# C_Arduino_MEGA2560_ref.net
KiCad netlist of a schematic drawn in EAGLE
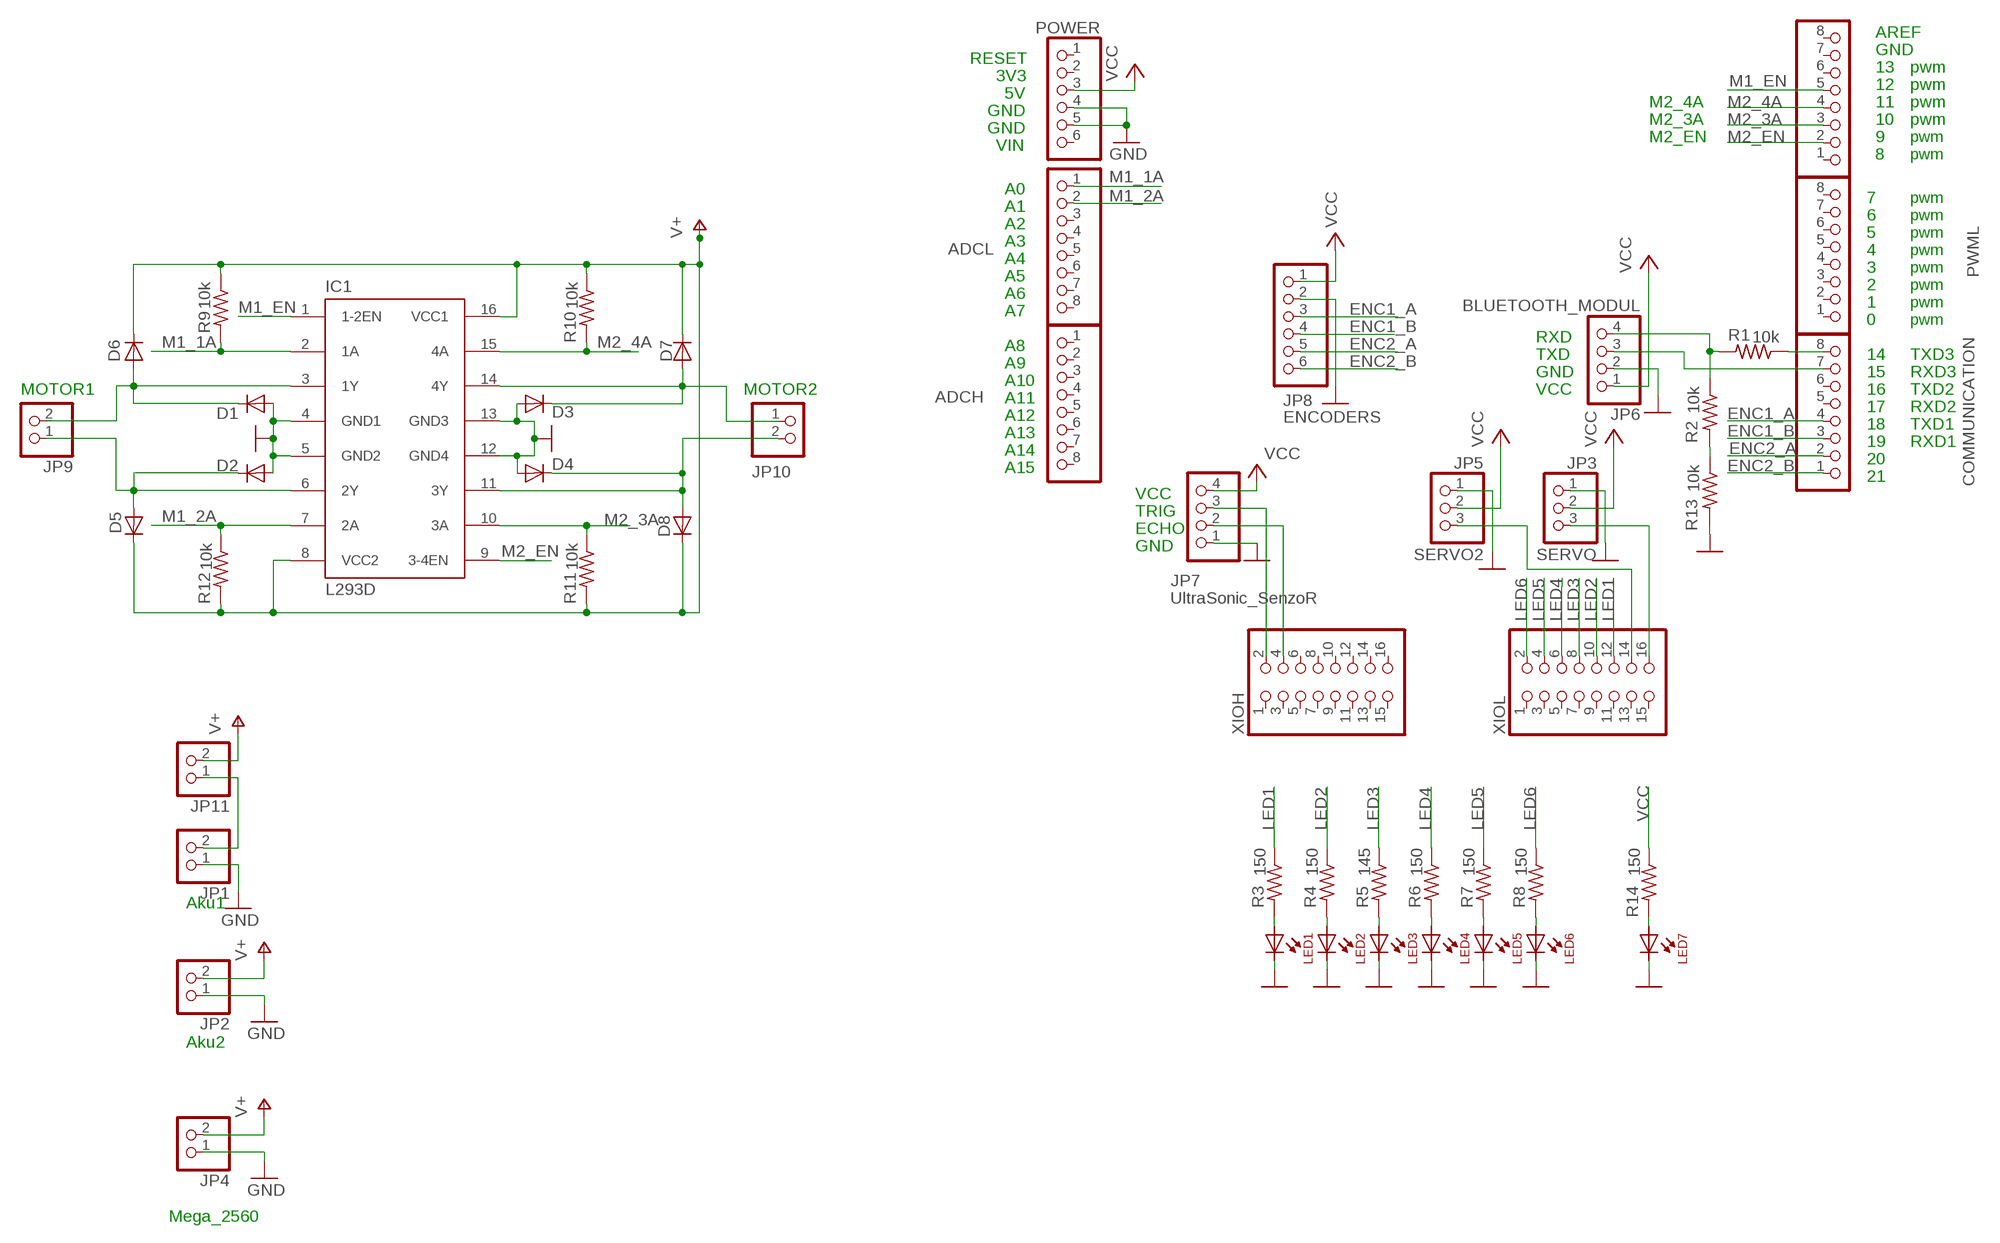
[diagram p0: schematic, sheet 1]

(export (version "E")
  (design (tool "Eeschema 10.0.6"))
  (components
    (comp (ref "ADCH")
      (value "PINHD-1X8")
      (footprint "eagle-import:1X08")
      (libsource (lib "eagle-import") (part "PINHD-1X8"))
    )
    (comp (ref "ADCL")
      (value "PINHD-1X8")
      (footprint "eagle-import:1X08")
      (libsource (lib "eagle-import") (part "PINHD-1X8"))
    )
    (comp (ref "COMMUNICATION")
      (value "PINHD-1X8")
      (footprint "eagle-import:1X08")
      (libsource (lib "eagle-import") (part "PINHD-1X8"))
    )
    (comp (ref "D1")
      (value "PMLL4150")
      (footprint "eagle-import:SOD80C")
      (libsource (lib "eagle-import") (part "PMLL4150"))
    )
    (comp (ref "D2")
      (value "PMLL4150")
      (footprint "eagle-import:SOD80C")
      (libsource (lib "eagle-import") (part "PMLL4150"))
    )
    (comp (ref "D3")
      (value "PMLL4150")
      (footprint "eagle-import:SOD80C")
      (libsource (lib "eagle-import") (part "PMLL4150"))
    )
    (comp (ref "D4")
      (value "PMLL4150")
      (footprint "eagle-import:SOD80C")
      (libsource (lib "eagle-import") (part "PMLL4150"))
    )
    (comp (ref "D5")
      (value "PMLL4150")
      (footprint "eagle-import:SOD80C")
      (libsource (lib "eagle-import") (part "PMLL4150"))
    )
    (comp (ref "D6")
      (value "PMLL4150")
      (footprint "eagle-import:SOD80C")
      (libsource (lib "eagle-import") (part "PMLL4150"))
    )
    (comp (ref "D7")
      (value "PMLL4150")
      (footprint "eagle-import:SOD80C")
      (libsource (lib "eagle-import") (part "PMLL4150"))
    )
    (comp (ref "D8")
      (value "PMLL4150")
      (footprint "eagle-import:SOD80C")
      (libsource (lib "eagle-import") (part "PMLL4150"))
    )
    (comp (ref "IC1")
      (value "L293D")
      (footprint "eagle-import:DIL16")
      (libsource (lib "eagle-import") (part "L293D"))
    )
    (comp (ref "JP1")
      (value "PINHD-1X2")
      (footprint "eagle-import:1X02")
      (libsource (lib "eagle-import") (part "PINHD-1X2"))
    )
    (comp (ref "JP2")
      (value "PINHD-1X2")
      (footprint "eagle-import:1X02")
      (libsource (lib "eagle-import") (part "PINHD-1X2"))
    )
    (comp (ref "JP3")
      (value "SERVO")
      (footprint "eagle-import:1X03")
      (libsource (lib "eagle-import") (part "PINHD-1X3"))
    )
    (comp (ref "JP4")
      (value "PINHD-1X2")
      (footprint "eagle-import:1X02")
      (libsource (lib "eagle-import") (part "PINHD-1X2"))
    )
    (comp (ref "JP5")
      (value "SERVO2")
      (footprint "eagle-import:1X03")
      (libsource (lib "eagle-import") (part "PINHD-1X3"))
    )
    (comp (ref "JP6")
      (value "BLUETOOTH_MODUL")
      (footprint "eagle-import:1X04")
      (libsource (lib "eagle-import") (part "PINHD-1X4"))
    )
    (comp (ref "JP7")
      (value "UltraSonic_SenzoR")
      (footprint "eagle-import:1X04")
      (libsource (lib "eagle-import") (part "PINHD-1X4"))
    )
    (comp (ref "JP8")
      (value "ENCODERS")
      (footprint "eagle-import:1X06")
      (libsource (lib "eagle-import") (part "PINHD-1X6"))
    )
    (comp (ref "JP9")
      (value "PINHD-1X2")
      (footprint "eagle-import:1X02")
      (libsource (lib "eagle-import") (part "PINHD-1X2"))
    )
    (comp (ref "JP10")
      (value "PINHD-1X2")
      (footprint "eagle-import:1X02")
      (libsource (lib "eagle-import") (part "PINHD-1X2"))
    )
    (comp (ref "JP11")
      (value "PINHD-1X2")
      (footprint "eagle-import:1X02")
      (libsource (lib "eagle-import") (part "PINHD-1X2"))
    )
    (comp (ref "LED1")
      (value "LED_Y_SMD")
      (footprint "eagle-import:LED_Y_SMD")
      (libsource (lib "eagle-import") (part "LED_Y_SMD"))
    )
    (comp (ref "LED2")
      (value "LED_Y_SMD")
      (footprint "eagle-import:LED_Y_SMD")
      (libsource (lib "eagle-import") (part "LED_Y_SMD"))
    )
    (comp (ref "LED3")
      (value "LED_Y_SMD")
      (footprint "eagle-import:LED_Y_SMD")
      (libsource (lib "eagle-import") (part "LED_Y_SMD"))
    )
    (comp (ref "LED4")
      (value "LED_Y_SMD")
      (footprint "eagle-import:LED_Y_SMD")
      (libsource (lib "eagle-import") (part "LED_Y_SMD"))
    )
    (comp (ref "LED5")
      (value "LED_Y_SMD")
      (footprint "eagle-import:LED_Y_SMD")
      (libsource (lib "eagle-import") (part "LED_Y_SMD"))
    )
    (comp (ref "LED6")
      (value "LED_Y_SMD")
      (footprint "eagle-import:LED_Y_SMD")
      (libsource (lib "eagle-import") (part "LED_Y_SMD"))
    )
    (comp (ref "LED7")
      (value "LED_Y_SMD")
      (footprint "eagle-import:LED_Y_SMD")
      (libsource (lib "eagle-import") (part "LED_Y_SMD"))
    )
    (comp (ref "POWER")
      (value "PINHD-1X6")
      (footprint "eagle-import:1X06")
      (libsource (lib "eagle-import") (part "PINHD-1X6"))
    )
    (comp (ref "PWMH")
      (value "PINHD-1X8")
      (footprint "eagle-import:1X08")
      (libsource (lib "eagle-import") (part "PINHD-1X8"))
    )
    (comp (ref "PWML")
      (value "PINHD-1X8")
      (footprint "eagle-import:1X08")
      (libsource (lib "eagle-import") (part "PINHD-1X8"))
    )
    (comp (ref "R1")
      (value "10k")
      (footprint "eagle-import:R0805")
      (libsource (lib "eagle-import") (part "R-US_R0805"))
    )
    (comp (ref "R2")
      (value "10k")
      (footprint "eagle-import:R0805")
      (libsource (lib "eagle-import") (part "R-US_R0805"))
    )
    (comp (ref "R3")
      (value "150")
      (footprint "eagle-import:R0805")
      (libsource (lib "eagle-import") (part "R-US_R0805"))
    )
    (comp (ref "R4")
      (value "150")
      (footprint "eagle-import:R0805")
      (libsource (lib "eagle-import") (part "R-US_R0805"))
    )
    (comp (ref "R5")
      (value "145")
      (footprint "eagle-import:R0805")
      (libsource (lib "eagle-import") (part "R-US_R0805"))
    )
    (comp (ref "R6")
      (value "150")
      (footprint "eagle-import:R0805")
      (libsource (lib "eagle-import") (part "R-US_R0805"))
    )
    (comp (ref "R7")
      (value "150")
      (footprint "eagle-import:R0805")
      (libsource (lib "eagle-import") (part "R-US_R0805"))
    )
    (comp (ref "R8")
      (value "150")
      (footprint "eagle-import:R0805")
      (libsource (lib "eagle-import") (part "R-US_R0805"))
    )
    (comp (ref "R9")
      (value "10k")
      (footprint "eagle-import:R0805")
      (libsource (lib "eagle-import") (part "R-US_R0805"))
    )
    (comp (ref "R10")
      (value "10k")
      (footprint "eagle-import:R0805")
      (libsource (lib "eagle-import") (part "R-US_R0805"))
    )
    (comp (ref "R11")
      (value "10k")
      (footprint "eagle-import:R0805")
      (libsource (lib "eagle-import") (part "R-US_R0805"))
    )
    (comp (ref "R12")
      (value "10k")
      (footprint "eagle-import:R0805")
      (libsource (lib "eagle-import") (part "R-US_R0805"))
    )
    (comp (ref "R13")
      (value "10k")
      (footprint "eagle-import:R0805")
      (libsource (lib "eagle-import") (part "R-US_R0805"))
    )
    (comp (ref "R14")
      (value "150")
      (footprint "eagle-import:R0805")
      (libsource (lib "eagle-import") (part "R-US_R0805"))
    )
    (comp (ref "XIOH")
      (value "PINHD-2X8")
      (footprint "eagle-import:2X08")
      (libsource (lib "eagle-import") (part "PINHD-2X8"))
    )
    (comp (ref "XIOL")
      (value "PINHD-2X8")
      (footprint "eagle-import:2X08")
      (libsource (lib "eagle-import") (part "PINHD-2X8"))
    )
  )
  (nets
    (net (code "1") (name "/ENC1_A") (class "Default")
      (node (ref "COMMUNICATION") (pin "4") (pinfunction "4_4") (pintype "passive"))
      (node (ref "JP8") (pin "3") (pinfunction "3_3") (pintype "passive"))
    )
    (net (code "2") (name "/ENC1_B") (class "Default")
      (node (ref "COMMUNICATION") (pin "3") (pinfunction "3_3") (pintype "passive"))
      (node (ref "JP8") (pin "4") (pinfunction "4_4") (pintype "passive"))
    )
    (net (code "3") (name "/ENC2_A") (class "Default")
      (node (ref "COMMUNICATION") (pin "2") (pinfunction "2_2") (pintype "passive"))
      (node (ref "JP8") (pin "5") (pinfunction "5_5") (pintype "passive"))
    )
    (net (code "4") (name "/ENC2_B") (class "Default")
      (node (ref "COMMUNICATION") (pin "1") (pinfunction "1_1") (pintype "passive"))
      (node (ref "JP8") (pin "6") (pinfunction "6_6") (pintype "passive"))
    )
    (net (code "5") (name "/LED1") (class "Default")
      (node (ref "R3") (pin "1") (pinfunction "1_1") (pintype "passive"))
      (node (ref "XIOL") (pin "12") (pinfunction "12_12") (pintype "passive"))
    )
    (net (code "6") (name "/LED2") (class "Default")
      (node (ref "R4") (pin "1") (pinfunction "1_1") (pintype "passive"))
      (node (ref "XIOL") (pin "10") (pinfunction "10_10") (pintype "passive"))
    )
    (net (code "7") (name "/LED3") (class "Default")
      (node (ref "R5") (pin "1") (pinfunction "1_1") (pintype "passive"))
      (node (ref "XIOL") (pin "8") (pinfunction "8_8") (pintype "passive"))
    )
    (net (code "8") (name "/LED4") (class "Default")
      (node (ref "R6") (pin "1") (pinfunction "1_1") (pintype "passive"))
      (node (ref "XIOL") (pin "6") (pinfunction "6_6") (pintype "passive"))
    )
    (net (code "9") (name "/LED5") (class "Default")
      (node (ref "R7") (pin "1") (pinfunction "1_1") (pintype "passive"))
      (node (ref "XIOL") (pin "4") (pinfunction "4_4") (pintype "passive"))
    )
    (net (code "10") (name "/LED6") (class "Default")
      (node (ref "R8") (pin "1") (pinfunction "1_1") (pintype "passive"))
      (node (ref "XIOL") (pin "2") (pinfunction "2_2") (pintype "passive"))
    )
    (net (code "11") (name "/M1_1A") (class "Default")
      (node (ref "ADCL") (pin "1") (pinfunction "1_1") (pintype "passive"))
      (node (ref "IC1") (pin "2") (pinfunction "1A_2") (pintype "input"))
      (node (ref "R9") (pin "2") (pinfunction "2_2") (pintype "passive"))
    )
    (net (code "12") (name "/M1_2A") (class "Default")
      (node (ref "ADCL") (pin "2") (pinfunction "2_2") (pintype "passive"))
      (node (ref "IC1") (pin "7") (pinfunction "2A_7") (pintype "input"))
      (node (ref "R12") (pin "1") (pinfunction "1_1") (pintype "passive"))
    )
    (net (code "13") (name "/M1_EN") (class "Default")
      (node (ref "IC1") (pin "1") (pinfunction "1-2EN_1") (pintype "input"))
      (node (ref "PWMH") (pin "5") (pinfunction "5_5") (pintype "passive"))
    )
    (net (code "14") (name "/M2_3A") (class "Default")
      (node (ref "IC1") (pin "10") (pinfunction "3A_10") (pintype "input"))
      (node (ref "PWMH") (pin "3") (pinfunction "3_3") (pintype "passive"))
      (node (ref "R11") (pin "1") (pinfunction "1_1") (pintype "passive"))
    )
    (net (code "15") (name "/M2_4A") (class "Default")
      (node (ref "IC1") (pin "15") (pinfunction "4A_15") (pintype "input"))
      (node (ref "PWMH") (pin "4") (pinfunction "4_4") (pintype "passive"))
      (node (ref "R10") (pin "2") (pinfunction "2_2") (pintype "passive"))
    )
    (net (code "16") (name "/M2_EN") (class "Default")
      (node (ref "IC1") (pin "9") (pinfunction "3-4EN_9") (pintype "input"))
      (node (ref "PWMH") (pin "2") (pinfunction "2_2") (pintype "passive"))
    )
    (net (code "17") (name "GND") (class "Default")
      (node (ref "D1") (pin "A") (pinfunction "A_A") (pintype "passive"))
      (node (ref "D2") (pin "A") (pinfunction "A_A") (pintype "passive"))
      (node (ref "D3") (pin "A") (pinfunction "A_A") (pintype "passive"))
      (node (ref "D4") (pin "A") (pinfunction "A_A") (pintype "passive"))
      (node (ref "IC1") (pin "12") (pinfunction "GND4_12") (pintype "power_in"))
      (node (ref "IC1") (pin "13") (pinfunction "GND3_13") (pintype "power_in"))
      (node (ref "IC1") (pin "4") (pinfunction "GND1_4") (pintype "power_in"))
      (node (ref "IC1") (pin "5") (pinfunction "GND2_5") (pintype "power_in"))
      (node (ref "JP1") (pin "1") (pinfunction "1_1") (pintype "passive"))
      (node (ref "JP2") (pin "1") (pinfunction "1_1") (pintype "passive"))
      (node (ref "JP3") (pin "1") (pinfunction "1_1") (pintype "passive"))
      (node (ref "JP4") (pin "1") (pinfunction "1_1") (pintype "passive"))
      (node (ref "JP5") (pin "1") (pinfunction "1_1") (pintype "passive"))
      (node (ref "JP6") (pin "2") (pinfunction "2_2") (pintype "passive"))
      (node (ref "JP7") (pin "1") (pinfunction "1_1") (pintype "passive"))
      (node (ref "JP8") (pin "2") (pinfunction "2_2") (pintype "passive"))
      (node (ref "LED1") (pin "CATHODE") (pinfunction "CATHODE_CATHODE") (pintype "bidirectional"))
      (node (ref "LED2") (pin "CATHODE") (pinfunction "CATHODE_CATHODE") (pintype "bidirectional"))
      (node (ref "LED3") (pin "CATHODE") (pinfunction "CATHODE_CATHODE") (pintype "bidirectional"))
      (node (ref "LED4") (pin "CATHODE") (pinfunction "CATHODE_CATHODE") (pintype "bidirectional"))
      (node (ref "LED5") (pin "CATHODE") (pinfunction "CATHODE_CATHODE") (pintype "bidirectional"))
      (node (ref "LED6") (pin "CATHODE") (pinfunction "CATHODE_CATHODE") (pintype "bidirectional"))
      (node (ref "LED7") (pin "CATHODE") (pinfunction "CATHODE_CATHODE") (pintype "bidirectional"))
      (node (ref "POWER") (pin "4") (pinfunction "4_4") (pintype "passive"))
      (node (ref "POWER") (pin "5") (pinfunction "5_5") (pintype "passive"))
      (node (ref "R13") (pin "2") (pinfunction "2_2") (pintype "passive"))
    )
    (net (code "18") (name "Net-(COMMUNICATION-Pad7)") (class "Default")
      (node (ref "COMMUNICATION") (pin "7") (pinfunction "7_7") (pintype "passive"))
      (node (ref "JP6") (pin "3") (pinfunction "3_3") (pintype "passive"))
    )
    (net (code "19") (name "Net-(COMMUNICATION-Pad8)") (class "Default")
      (node (ref "COMMUNICATION") (pin "8") (pinfunction "8_8") (pintype "passive"))
      (node (ref "R1") (pin "1") (pinfunction "1_1") (pintype "passive"))
    )
    (net (code "20") (name "Net-(IC1-1Y)") (class "Default")
      (node (ref "D1") (pin "C") (pinfunction "C_C") (pintype "passive"))
      (node (ref "D6") (pin "A") (pinfunction "A_A") (pintype "passive"))
      (node (ref "IC1") (pin "3") (pinfunction "1Y_3") (pintype "output"))
      (node (ref "JP9") (pin "2") (pinfunction "2_2") (pintype "passive"))
    )
    (net (code "21") (name "Net-(IC1-2Y)") (class "Default")
      (node (ref "D2") (pin "C") (pinfunction "C_C") (pintype "passive"))
      (node (ref "D5") (pin "A") (pinfunction "A_A") (pintype "passive"))
      (node (ref "IC1") (pin "6") (pinfunction "2Y_6") (pintype "output"))
      (node (ref "JP9") (pin "1") (pinfunction "1_1") (pintype "passive"))
    )
    (net (code "22") (name "Net-(IC1-3Y)") (class "Default")
      (node (ref "D4") (pin "C") (pinfunction "C_C") (pintype "passive"))
      (node (ref "D8") (pin "A") (pinfunction "A_A") (pintype "passive"))
      (node (ref "IC1") (pin "11") (pinfunction "3Y_11") (pintype "output"))
      (node (ref "JP10") (pin "2") (pinfunction "2_2") (pintype "passive"))
    )
    (net (code "23") (name "Net-(IC1-4Y)") (class "Default")
      (node (ref "D3") (pin "C") (pinfunction "C_C") (pintype "passive"))
      (node (ref "D7") (pin "A") (pinfunction "A_A") (pintype "passive"))
      (node (ref "IC1") (pin "14") (pinfunction "4Y_14") (pintype "output"))
      (node (ref "JP10") (pin "1") (pinfunction "1_1") (pintype "passive"))
    )
    (net (code "24") (name "Net-(JP1-Pad2)") (class "Default")
      (node (ref "JP1") (pin "2") (pinfunction "2_2") (pintype "passive"))
      (node (ref "JP11") (pin "1") (pinfunction "1_1") (pintype "passive"))
    )
    (net (code "25") (name "Net-(JP3-Pad3)") (class "Default")
      (node (ref "JP3") (pin "3") (pinfunction "3_3") (pintype "passive"))
      (node (ref "XIOL") (pin "16") (pinfunction "16_16") (pintype "passive"))
    )
    (net (code "26") (name "Net-(JP5-Pad3)") (class "Default")
      (node (ref "JP5") (pin "3") (pinfunction "3_3") (pintype "passive"))
      (node (ref "XIOL") (pin "14") (pinfunction "14_14") (pintype "passive"))
    )
    (net (code "27") (name "Net-(JP6-Pad4)") (class "Default")
      (node (ref "JP6") (pin "4") (pinfunction "4_4") (pintype "passive"))
      (node (ref "R1") (pin "2") (pinfunction "2_2") (pintype "passive"))
      (node (ref "R2") (pin "1") (pinfunction "1_1") (pintype "passive"))
    )
    (net (code "28") (name "Net-(JP7-Pad2)") (class "Default")
      (node (ref "JP7") (pin "2") (pinfunction "2_2") (pintype "passive"))
      (node (ref "XIOH") (pin "4") (pinfunction "4_4") (pintype "passive"))
    )
    (net (code "29") (name "Net-(JP7-Pad3)") (class "Default")
      (node (ref "JP7") (pin "3") (pinfunction "3_3") (pintype "passive"))
      (node (ref "XIOH") (pin "2") (pinfunction "2_2") (pintype "passive"))
    )
    (net (code "30") (name "Net-(LED1-PadANODE)") (class "Default")
      (node (ref "LED1") (pin "ANODE") (pinfunction "ANODE_ANODE") (pintype "bidirectional"))
      (node (ref "R3") (pin "2") (pinfunction "2_2") (pintype "passive"))
    )
    (net (code "31") (name "Net-(LED2-PadANODE)") (class "Default")
      (node (ref "LED2") (pin "ANODE") (pinfunction "ANODE_ANODE") (pintype "bidirectional"))
      (node (ref "R4") (pin "2") (pinfunction "2_2") (pintype "passive"))
    )
    (net (code "32") (name "Net-(LED3-PadANODE)") (class "Default")
      (node (ref "LED3") (pin "ANODE") (pinfunction "ANODE_ANODE") (pintype "bidirectional"))
      (node (ref "R5") (pin "2") (pinfunction "2_2") (pintype "passive"))
    )
    (net (code "33") (name "Net-(LED4-PadANODE)") (class "Default")
      (node (ref "LED4") (pin "ANODE") (pinfunction "ANODE_ANODE") (pintype "bidirectional"))
      (node (ref "R6") (pin "2") (pinfunction "2_2") (pintype "passive"))
    )
    (net (code "34") (name "Net-(LED5-PadANODE)") (class "Default")
      (node (ref "LED5") (pin "ANODE") (pinfunction "ANODE_ANODE") (pintype "bidirectional"))
      (node (ref "R7") (pin "2") (pinfunction "2_2") (pintype "passive"))
    )
    (net (code "35") (name "Net-(LED6-PadANODE)") (class "Default")
      (node (ref "LED6") (pin "ANODE") (pinfunction "ANODE_ANODE") (pintype "bidirectional"))
      (node (ref "R8") (pin "2") (pinfunction "2_2") (pintype "passive"))
    )
    (net (code "36") (name "Net-(LED7-PadANODE)") (class "Default")
      (node (ref "LED7") (pin "ANODE") (pinfunction "ANODE_ANODE") (pintype "bidirectional"))
      (node (ref "R14") (pin "2") (pinfunction "2_2") (pintype "passive"))
    )
    (net (code "37") (name "Net-(R13-Pad1)") (class "Default")
      (node (ref "R13") (pin "1") (pinfunction "1_1") (pintype "passive"))
      (node (ref "R2") (pin "2") (pinfunction "2_2") (pintype "passive"))
    )
    (net (code "38") (name "V+") (class "Default")
      (node (ref "D5") (pin "C") (pinfunction "C_C") (pintype "passive"))
      (node (ref "D6") (pin "C") (pinfunction "C_C") (pintype "passive"))
      (node (ref "D7") (pin "C") (pinfunction "C_C") (pintype "passive"))
      (node (ref "D8") (pin "C") (pinfunction "C_C") (pintype "passive"))
      (node (ref "IC1") (pin "16") (pinfunction "VCC1_16") (pintype "power_in"))
      (node (ref "IC1") (pin "8") (pinfunction "VCC2_8") (pintype "power_in"))
      (node (ref "JP11") (pin "2") (pinfunction "2_2") (pintype "passive"))
      (node (ref "JP2") (pin "2") (pinfunction "2_2") (pintype "passive"))
      (node (ref "JP4") (pin "2") (pinfunction "2_2") (pintype "passive"))
      (node (ref "R10") (pin "1") (pinfunction "1_1") (pintype "passive"))
      (node (ref "R11") (pin "2") (pinfunction "2_2") (pintype "passive"))
      (node (ref "R12") (pin "2") (pinfunction "2_2") (pintype "passive"))
      (node (ref "R9") (pin "1") (pinfunction "1_1") (pintype "passive"))
    )
    (net (code "39") (name "VCC") (class "Default")
      (node (ref "JP3") (pin "2") (pinfunction "2_2") (pintype "passive"))
      (node (ref "JP5") (pin "2") (pinfunction "2_2") (pintype "passive"))
      (node (ref "JP6") (pin "1") (pinfunction "1_1") (pintype "passive"))
      (node (ref "JP7") (pin "4") (pinfunction "4_4") (pintype "passive"))
      (node (ref "JP8") (pin "1") (pinfunction "1_1") (pintype "passive"))
      (node (ref "POWER") (pin "3") (pinfunction "3_3") (pintype "passive"))
      (node (ref "R14") (pin "1") (pinfunction "1_1") (pintype "passive"))
    )
    (net (code "40") (name "unconnected-(ADCH-Pad1)") (class "Default")
      (node (ref "ADCH") (pin "1") (pinfunction "1_1") (pintype "passive"))
    )
    (net (code "41") (name "unconnected-(ADCH-Pad2)") (class "Default")
      (node (ref "ADCH") (pin "2") (pinfunction "2_2") (pintype "passive"))
    )
    (net (code "42") (name "unconnected-(ADCH-Pad3)") (class "Default")
      (node (ref "ADCH") (pin "3") (pinfunction "3_3") (pintype "passive"))
    )
    (net (code "43") (name "unconnected-(ADCH-Pad4)") (class "Default")
      (node (ref "ADCH") (pin "4") (pinfunction "4_4") (pintype "passive"))
    )
    (net (code "44") (name "unconnected-(ADCH-Pad5)") (class "Default")
      (node (ref "ADCH") (pin "5") (pinfunction "5_5") (pintype "passive"))
    )
    (net (code "45") (name "unconnected-(ADCH-Pad6)") (class "Default")
      (node (ref "ADCH") (pin "6") (pinfunction "6_6") (pintype "passive"))
    )
    (net (code "46") (name "unconnected-(ADCH-Pad7)") (class "Default")
      (node (ref "ADCH") (pin "7") (pinfunction "7_7") (pintype "passive"))
    )
    (net (code "47") (name "unconnected-(ADCH-Pad8)") (class "Default")
      (node (ref "ADCH") (pin "8") (pinfunction "8_8") (pintype "passive"))
    )
    (net (code "48") (name "unconnected-(ADCL-Pad3)") (class "Default")
      (node (ref "ADCL") (pin "3") (pinfunction "3_3") (pintype "passive"))
    )
    (net (code "49") (name "unconnected-(ADCL-Pad4)") (class "Default")
      (node (ref "ADCL") (pin "4") (pinfunction "4_4") (pintype "passive"))
    )
    (net (code "50") (name "unconnected-(ADCL-Pad5)") (class "Default")
      (node (ref "ADCL") (pin "5") (pinfunction "5_5") (pintype "passive"))
    )
    (net (code "51") (name "unconnected-(ADCL-Pad6)") (class "Default")
      (node (ref "ADCL") (pin "6") (pinfunction "6_6") (pintype "passive"))
    )
    (net (code "52") (name "unconnected-(ADCL-Pad7)") (class "Default")
      (node (ref "ADCL") (pin "7") (pinfunction "7_7") (pintype "passive"))
    )
    (net (code "53") (name "unconnected-(ADCL-Pad8)") (class "Default")
      (node (ref "ADCL") (pin "8") (pinfunction "8_8") (pintype "passive"))
    )
    (net (code "54") (name "unconnected-(COMMUNICATION-Pad5)") (class "Default")
      (node (ref "COMMUNICATION") (pin "5") (pinfunction "5_5") (pintype "passive"))
    )
    (net (code "55") (name "unconnected-(COMMUNICATION-Pad6)") (class "Default")
      (node (ref "COMMUNICATION") (pin "6") (pinfunction "6_6") (pintype "passive"))
    )
    (net (code "56") (name "unconnected-(POWER-Pad1)") (class "Default")
      (node (ref "POWER") (pin "1") (pinfunction "1_1") (pintype "passive"))
    )
    (net (code "57") (name "unconnected-(POWER-Pad2)") (class "Default")
      (node (ref "POWER") (pin "2") (pinfunction "2_2") (pintype "passive"))
    )
    (net (code "58") (name "unconnected-(POWER-Pad6)") (class "Default")
      (node (ref "POWER") (pin "6") (pinfunction "6_6") (pintype "passive"))
    )
    (net (code "59") (name "unconnected-(PWMH-Pad1)") (class "Default")
      (node (ref "PWMH") (pin "1") (pinfunction "1_1") (pintype "passive"))
    )
    (net (code "60") (name "unconnected-(PWMH-Pad6)") (class "Default")
      (node (ref "PWMH") (pin "6") (pinfunction "6_6") (pintype "passive"))
    )
    (net (code "61") (name "unconnected-(PWMH-Pad7)") (class "Default")
      (node (ref "PWMH") (pin "7") (pinfunction "7_7") (pintype "passive"))
    )
    (net (code "62") (name "unconnected-(PWMH-Pad8)") (class "Default")
      (node (ref "PWMH") (pin "8") (pinfunction "8_8") (pintype "passive"))
    )
    (net (code "63") (name "unconnected-(PWML-Pad1)") (class "Default")
      (node (ref "PWML") (pin "1") (pinfunction "1_1") (pintype "passive"))
    )
    (net (code "64") (name "unconnected-(PWML-Pad2)") (class "Default")
      (node (ref "PWML") (pin "2") (pinfunction "2_2") (pintype "passive"))
    )
    (net (code "65") (name "unconnected-(PWML-Pad3)") (class "Default")
      (node (ref "PWML") (pin "3") (pinfunction "3_3") (pintype "passive"))
    )
    (net (code "66") (name "unconnected-(PWML-Pad4)") (class "Default")
      (node (ref "PWML") (pin "4") (pinfunction "4_4") (pintype "passive"))
    )
    (net (code "67") (name "unconnected-(PWML-Pad5)") (class "Default")
      (node (ref "PWML") (pin "5") (pinfunction "5_5") (pintype "passive"))
    )
    (net (code "68") (name "unconnected-(PWML-Pad6)") (class "Default")
      (node (ref "PWML") (pin "6") (pinfunction "6_6") (pintype "passive"))
    )
    (net (code "69") (name "unconnected-(PWML-Pad7)") (class "Default")
      (node (ref "PWML") (pin "7") (pinfunction "7_7") (pintype "passive"))
    )
    (net (code "70") (name "unconnected-(PWML-Pad8)") (class "Default")
      (node (ref "PWML") (pin "8") (pinfunction "8_8") (pintype "passive"))
    )
    (net (code "71") (name "unconnected-(XIOH-Pad1)") (class "Default")
      (node (ref "XIOH") (pin "1") (pinfunction "1_1") (pintype "passive"))
    )
    (net (code "72") (name "unconnected-(XIOH-Pad3)") (class "Default")
      (node (ref "XIOH") (pin "3") (pinfunction "3_3") (pintype "passive"))
    )
    (net (code "73") (name "unconnected-(XIOH-Pad5)") (class "Default")
      (node (ref "XIOH") (pin "5") (pinfunction "5_5") (pintype "passive"))
    )
    (net (code "74") (name "unconnected-(XIOH-Pad6)") (class "Default")
      (node (ref "XIOH") (pin "6") (pinfunction "6_6") (pintype "passive"))
    )
    (net (code "75") (name "unconnected-(XIOH-Pad7)") (class "Default")
      (node (ref "XIOH") (pin "7") (pinfunction "7_7") (pintype "passive"))
    )
    (net (code "76") (name "unconnected-(XIOH-Pad8)") (class "Default")
      (node (ref "XIOH") (pin "8") (pinfunction "8_8") (pintype "passive"))
    )
    (net (code "77") (name "unconnected-(XIOH-Pad9)") (class "Default")
      (node (ref "XIOH") (pin "9") (pinfunction "9_9") (pintype "passive"))
    )
    (net (code "78") (name "unconnected-(XIOH-Pad10)") (class "Default")
      (node (ref "XIOH") (pin "10") (pinfunction "10_10") (pintype "passive"))
    )
    (net (code "79") (name "unconnected-(XIOH-Pad11)") (class "Default")
      (node (ref "XIOH") (pin "11") (pinfunction "11_11") (pintype "passive"))
    )
    (net (code "80") (name "unconnected-(XIOH-Pad12)") (class "Default")
      (node (ref "XIOH") (pin "12") (pinfunction "12_12") (pintype "passive"))
    )
    (net (code "81") (name "unconnected-(XIOH-Pad13)") (class "Default")
      (node (ref "XIOH") (pin "13") (pinfunction "13_13") (pintype "passive"))
    )
    (net (code "82") (name "unconnected-(XIOH-Pad14)") (class "Default")
      (node (ref "XIOH") (pin "14") (pinfunction "14_14") (pintype "passive"))
    )
    (net (code "83") (name "unconnected-(XIOH-Pad15)") (class "Default")
      (node (ref "XIOH") (pin "15") (pinfunction "15_15") (pintype "passive"))
    )
    (net (code "84") (name "unconnected-(XIOH-Pad16)") (class "Default")
      (node (ref "XIOH") (pin "16") (pinfunction "16_16") (pintype "passive"))
    )
    (net (code "85") (name "unconnected-(XIOL-Pad1)") (class "Default")
      (node (ref "XIOL") (pin "1") (pinfunction "1_1") (pintype "passive"))
    )
    (net (code "86") (name "unconnected-(XIOL-Pad3)") (class "Default")
      (node (ref "XIOL") (pin "3") (pinfunction "3_3") (pintype "passive"))
    )
    (net (code "87") (name "unconnected-(XIOL-Pad5)") (class "Default")
      (node (ref "XIOL") (pin "5") (pinfunction "5_5") (pintype "passive"))
    )
    (net (code "88") (name "unconnected-(XIOL-Pad7)") (class "Default")
      (node (ref "XIOL") (pin "7") (pinfunction "7_7") (pintype "passive"))
    )
    (net (code "89") (name "unconnected-(XIOL-Pad9)") (class "Default")
      (node (ref "XIOL") (pin "9") (pinfunction "9_9") (pintype "passive"))
    )
    (net (code "90") (name "unconnected-(XIOL-Pad11)") (class "Default")
      (node (ref "XIOL") (pin "11") (pinfunction "11_11") (pintype "passive"))
    )
    (net (code "91") (name "unconnected-(XIOL-Pad13)") (class "Default")
      (node (ref "XIOL") (pin "13") (pinfunction "13_13") (pintype "passive"))
    )
    (net (code "92") (name "unconnected-(XIOL-Pad15)") (class "Default")
      (node (ref "XIOL") (pin "15") (pinfunction "15_15") (pintype "passive"))
    )
  )
)
